# NixieTherm_v1_03.net
KiCad netlist of a schematic drawn in EAGLE
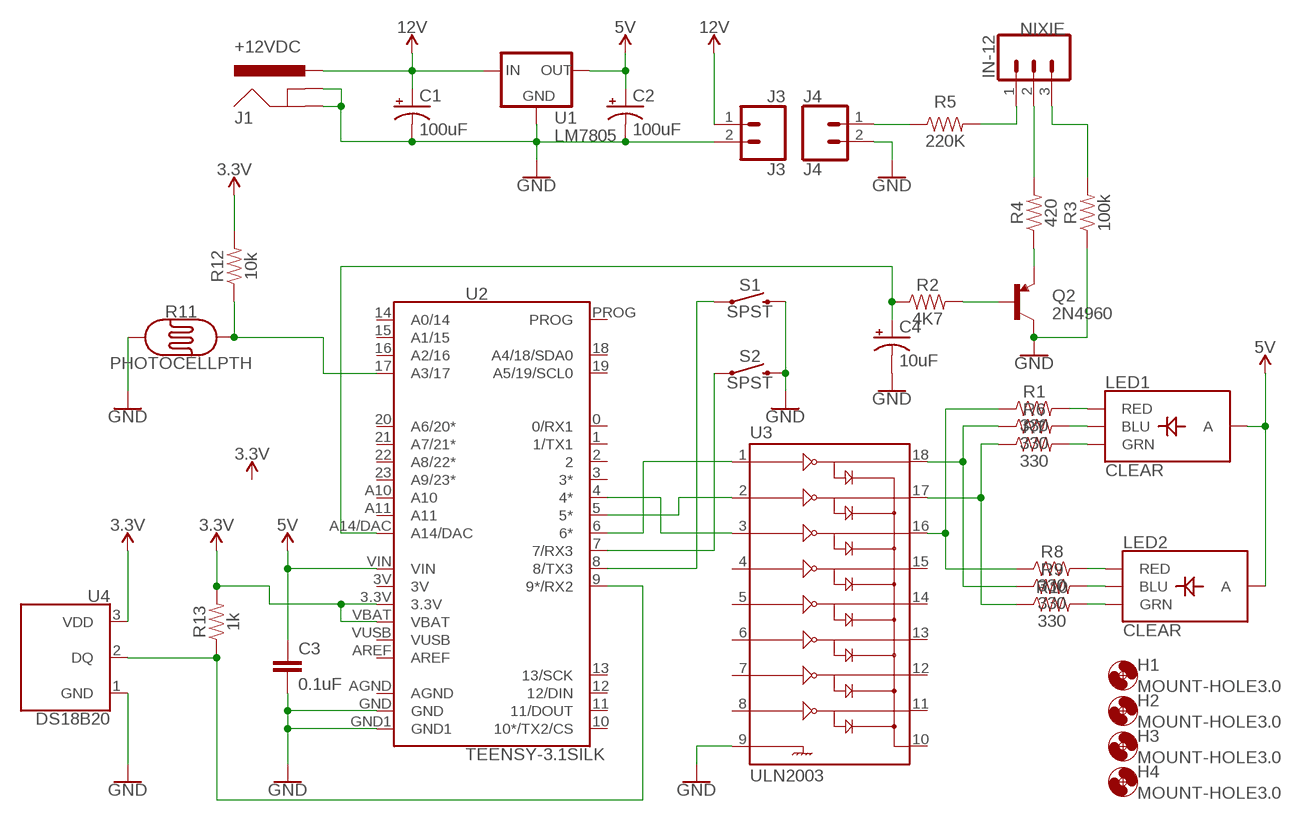
[diagram p0: schematic, sheet 1]

(export (version "E")
  (design (tool "Eeschema 10.0.6"))
  (components
    (comp (ref "C1")
      (value "100uF")
      (footprint "eagle-import:CPOL-RADIAL-2.5MM-6.5MM")
      (libsource (lib "eagle-import") (part "100UF-POLAR-RADIAL-2.5MM-25V-20%"))
    )
    (comp (ref "C2")
      (value "100uF")
      (footprint "eagle-import:CPOL-RADIAL-2.5MM-6.5MM")
      (libsource (lib "eagle-import") (part "100UF-POLAR-RADIAL-2.5MM-25V-20%"))
    )
    (comp (ref "C3")
      (value "0.1uF")
      (footprint "eagle-import:CAP-PTH-SMALL-KIT")
      (libsource (lib "eagle-import") (part "0.1UF-KIT-EZ-50V-20%"))
    )
    (comp (ref "C4")
      (value "10uF")
      (footprint "eagle-import:CPOL-RADIAL-2.5MM-5MM")
      (libsource (lib "eagle-import") (part "10UF-POLAR-RADIAL-2.5MM-25V-20%"))
    )
    (comp (ref "H1")
      (value "MOUNT-HOLE3.0")
      (footprint "eagle-import:3,0")
      (libsource (lib "eagle-import") (part "MOUNT-HOLE3.0"))
    )
    (comp (ref "H2")
      (value "MOUNT-HOLE3.0")
      (footprint "eagle-import:3,0")
      (libsource (lib "eagle-import") (part "MOUNT-HOLE3.0"))
    )
    (comp (ref "H3")
      (value "MOUNT-HOLE3.0")
      (footprint "eagle-import:3,0")
      (libsource (lib "eagle-import") (part "MOUNT-HOLE3.0"))
    )
    (comp (ref "H4")
      (value "MOUNT-HOLE3.0")
      (footprint "eagle-import:3,0")
      (libsource (lib "eagle-import") (part "MOUNT-HOLE3.0"))
    )
    (comp (ref "J1")
      (value "+12VDC")
      (footprint "eagle-import:POWER_JACK_PTH")
      (libsource (lib "eagle-import") (part "POWER_JACK"))
    )
    (comp (ref "J3")
      (value "J3")
      (footprint "eagle-import:1X02")
      (libsource (lib "eagle-import") (part "CONN_02"))
    )
    (comp (ref "J4")
      (value "J4")
      (footprint "eagle-import:1X02")
      (libsource (lib "eagle-import") (part "CONN_02"))
    )
    (comp (ref "LED1")
      (value "CLEAR")
      (footprint "eagle-import:LED-RGB-THRU")
      (libsource (lib "eagle-import") (part "LED-RGB-CACLEAR"))
    )
    (comp (ref "LED2")
      (value "CLEAR")
      (footprint "eagle-import:LED-RGB-THRU")
      (libsource (lib "eagle-import") (part "LED-RGB-CACLEAR"))
    )
    (comp (ref "NIXIE")
      (value "IN-12")
      (footprint "eagle-import:1X03_NO_SILK")
      (libsource (lib "eagle-import") (part "CONN_031X03_NO_SILK"))
    )
    (comp (ref "Q2")
      (value "2N4960")
      (footprint "eagle-import:TO-92")
      (libsource (lib "eagle-import") (part "TRANSISTOR_PNPTO92"))
    )
    (comp (ref "R1")
      (value "330")
      (footprint "eagle-import:AXIAL-0.3")
      (libsource (lib "eagle-import") (part "1KOHM-HORIZ-1/4W-1%"))
    )
    (comp (ref "R2")
      (value "4K7")
      (footprint "eagle-import:AXIAL-0.3")
      (libsource (lib "eagle-import") (part "100KOHM-HORIZ-1/4W-1%"))
    )
    (comp (ref "R3")
      (value "100k")
      (footprint "eagle-import:AXIAL-0.3")
      (libsource (lib "eagle-import") (part "100KOHM-HORIZ-1/4W-1%"))
    )
    (comp (ref "R4")
      (value "420")
      (footprint "eagle-import:AXIAL-0.3")
      (libsource (lib "eagle-import") (part "100KOHM-HORIZ-1/4W-1%"))
    )
    (comp (ref "R5")
      (value "220K")
      (footprint "eagle-import:AXIAL-0.3")
      (libsource (lib "eagle-import") (part "100KOHM-HORIZ-1/4W-1%"))
    )
    (comp (ref "R6")
      (value "330")
      (footprint "eagle-import:AXIAL-0.3")
      (libsource (lib "eagle-import") (part "1KOHM-HORIZ-1/4W-1%"))
    )
    (comp (ref "R7")
      (value "330")
      (footprint "eagle-import:AXIAL-0.3")
      (libsource (lib "eagle-import") (part "1KOHM-HORIZ-1/4W-1%"))
    )
    (comp (ref "R8")
      (value "330")
      (footprint "eagle-import:AXIAL-0.3")
      (libsource (lib "eagle-import") (part "1KOHM-HORIZ-1/4W-1%"))
    )
    (comp (ref "R9")
      (value "330")
      (footprint "eagle-import:AXIAL-0.3")
      (libsource (lib "eagle-import") (part "1KOHM-HORIZ-1/4W-1%"))
    )
    (comp (ref "R10")
      (value "330")
      (footprint "eagle-import:AXIAL-0.3")
      (libsource (lib "eagle-import") (part "1KOHM-HORIZ-1/4W-1%"))
    )
    (comp (ref "R11")
      (value "PHOTOCELLPTH")
      (footprint "eagle-import:PHOTOCELL")
      (libsource (lib "eagle-import") (part "PHOTOCELLPTH"))
    )
    (comp (ref "R12")
      (value "10k")
      (footprint "eagle-import:AXIAL-0.3")
      (libsource (lib "eagle-import") (part "10KOHM-HORIZ-1/4W-1%"))
    )
    (comp (ref "R13")
      (value "1k")
      (footprint "eagle-import:AXIAL-0.3")
      (libsource (lib "eagle-import") (part "1KOHM-HORIZ-1/4W-1%"))
    )
    (comp (ref "S1")
      (value "SPST")
      (footprint "eagle-import:TACTILE_SWITCH_PTH_6.0MM")
      (libsource (lib "eagle-import") (part "MOMENTARY-SWITCH-SPST-PTH-6.0MM"))
    )
    (comp (ref "S2")
      (value "SPST")
      (footprint "eagle-import:TACTILE_SWITCH_PTH_6.0MM")
      (libsource (lib "eagle-import") (part "MOMENTARY-SWITCH-SPST-PTH-6.0MM"))
    )
    (comp (ref "U1")
      (value "LM7805")
      (footprint "eagle-import:TO-220-ALT")
      (libsource (lib "eagle-import") (part "V_REG_78XX-TO-220"))
    )
    (comp (ref "U2")
      (value "TEENSY-3.1SILK")
      (footprint "eagle-import:TEENSY-3.1")
      (libsource (lib "eagle-import") (part "TEENSY-3.1SILK"))
    )
    (comp (ref "U3")
      (value "ULN2003")
      (footprint "eagle-import:DIL18")
      (libsource (lib "eagle-import") (part "ULN2803DIP"))
    )
    (comp (ref "U4")
      (value "DS18B20")
      (footprint "eagle-import:TO-92-AMMO")
      (libsource (lib "eagle-import") (part "DS18B20"))
    )
  )
  (nets
    (net (code "1") (name "/3V") (class "Default")
      (node (ref "U2") (pin "3V") (pinfunction "3V_3V") (pintype "power_in"))
    )
    (net (code "2") (name "/AGND") (class "Default")
      (node (ref "U2") (pin "AGND") (pinfunction "AGND_AGND") (pintype "power_in"))
    )
    (net (code "3") (name "/VUSB") (class "Default")
      (node (ref "U2") (pin "VUSB") (pinfunction "VUSB_VUSB") (pintype "power_in"))
    )
    (net (code "4") (name "3.3V") (class "Default")
      (node (ref "R12") (pin "P$2") (pinfunction "2_P$2") (pintype "passive"))
      (node (ref "R13") (pin "P$2") (pinfunction "2_P$2") (pintype "passive"))
      (node (ref "U2") (pin "3.3V") (pinfunction "3.3V_3.3V") (pintype "power_in"))
      (node (ref "U2") (pin "VBAT") (pinfunction "VBAT_VBAT") (pintype "power_in"))
      (node (ref "U4") (pin "3") (pinfunction "VDD_3") (pintype "power_in"))
    )
    (net (code "5") (name "5V") (class "Default")
      (node (ref "C2") (pin "1") (pinfunction "+_1") (pintype "passive"))
      (node (ref "C3") (pin "1") (pinfunction "1_1") (pintype "passive"))
      (node (ref "LED1") (pin "2") (pinfunction "A_2") (pintype "bidirectional"))
      (node (ref "LED2") (pin "2") (pinfunction "A_2") (pintype "bidirectional"))
      (node (ref "U1") (pin "OUT") (pinfunction "OUT_OUT") (pintype "passive"))
      (node (ref "U2") (pin "VIN") (pinfunction "VIN_VIN") (pintype "power_in"))
    )
    (net (code "6") (name "12V") (class "Default")
      (node (ref "C1") (pin "1") (pinfunction "+_1") (pintype "passive"))
      (node (ref "J1") (pin "PWR") (pinfunction "PWR_PWR") (pintype "bidirectional"))
      (node (ref "J3") (pin "1") (pinfunction "1_1") (pintype "passive"))
      (node (ref "U1") (pin "IN") (pinfunction "IN_IN") (pintype "input"))
    )
    (net (code "7") (name "GND") (class "Default")
      (node (ref "C1") (pin "2") (pinfunction "-_2") (pintype "passive"))
      (node (ref "C2") (pin "2") (pinfunction "-_2") (pintype "passive"))
      (node (ref "C3") (pin "2") (pinfunction "2_2") (pintype "passive"))
      (node (ref "C4") (pin "2") (pinfunction "-_2") (pintype "passive"))
      (node (ref "J1") (pin "GND") (pinfunction "GND_GND") (pintype "bidirectional"))
      (node (ref "J1") (pin "GNDBREAK") (pinfunction "GNDBREAK_GNDBREAK") (pintype "bidirectional"))
      (node (ref "J3") (pin "2") (pinfunction "2_2") (pintype "passive"))
      (node (ref "J4") (pin "2") (pinfunction "2_2") (pintype "passive"))
      (node (ref "Q2") (pin "3") (pinfunction "C_3") (pintype "passive"))
      (node (ref "R11") (pin "1") (pinfunction "P$1_1") (pintype "bidirectional"))
      (node (ref "R3") (pin "P$1") (pinfunction "1_P$1") (pintype "passive"))
      (node (ref "S1") (pin "3") (pinfunction "2_3") (pintype "passive"))
      (node (ref "S2") (pin "3") (pinfunction "2_3") (pintype "passive"))
      (node (ref "U1") (pin "GND") (pinfunction "GND_GND") (pintype "input"))
      (node (ref "U2") (pin "GND") (pinfunction "GND_GND") (pintype "power_in"))
      (node (ref "U2") (pin "GND1") (pinfunction "GND1_GND1") (pintype "power_in"))
      (node (ref "U3") (pin "9") (pinfunction "9_9") (pintype "bidirectional"))
      (node (ref "U4") (pin "1") (pinfunction "GND_1") (pintype "power_in"))
    )
    (net (code "8") (name "Net-(C4-+)") (class "Default")
      (node (ref "C4") (pin "1") (pinfunction "+_1") (pintype "passive"))
      (node (ref "R2") (pin "P$1") (pinfunction "1_P$1") (pintype "passive"))
      (node (ref "U2") (pin "A14/DAC") (pinfunction "A14/DAC_A14/DAC") (pintype "bidirectional"))
    )
    (net (code "9") (name "Net-(LED1-BLU)") (class "Default")
      (node (ref "LED1") (pin "4") (pinfunction "BLU_4") (pintype "bidirectional"))
      (node (ref "R6") (pin "P$2") (pinfunction "2_P$2") (pintype "passive"))
    )
    (net (code "10") (name "Net-(LED1-GRN)") (class "Default")
      (node (ref "LED1") (pin "3") (pinfunction "GRN_3") (pintype "bidirectional"))
      (node (ref "R7") (pin "P$2") (pinfunction "2_P$2") (pintype "passive"))
    )
    (net (code "11") (name "Net-(LED1-RED)") (class "Default")
      (node (ref "LED1") (pin "1") (pinfunction "RED_1") (pintype "bidirectional"))
      (node (ref "R1") (pin "P$2") (pinfunction "2_P$2") (pintype "passive"))
    )
    (net (code "12") (name "Net-(LED2-BLU)") (class "Default")
      (node (ref "LED2") (pin "4") (pinfunction "BLU_4") (pintype "bidirectional"))
      (node (ref "R9") (pin "P$2") (pinfunction "2_P$2") (pintype "passive"))
    )
    (net (code "13") (name "Net-(LED2-GRN)") (class "Default")
      (node (ref "LED2") (pin "3") (pinfunction "GRN_3") (pintype "bidirectional"))
      (node (ref "R10") (pin "P$2") (pinfunction "2_P$2") (pintype "passive"))
    )
    (net (code "14") (name "Net-(LED2-RED)") (class "Default")
      (node (ref "LED2") (pin "1") (pinfunction "RED_1") (pintype "bidirectional"))
      (node (ref "R8") (pin "P$2") (pinfunction "2_P$2") (pintype "passive"))
    )
    (net (code "15") (name "Net-(Q2-B)") (class "Default")
      (node (ref "Q2") (pin "2") (pinfunction "B_2") (pintype "passive"))
      (node (ref "R2") (pin "P$2") (pinfunction "2_P$2") (pintype "passive"))
    )
    (net (code "16") (name "Net-(Q2-E)") (class "Default")
      (node (ref "Q2") (pin "1") (pinfunction "E_1") (pintype "passive"))
      (node (ref "R4") (pin "P$1") (pinfunction "1_P$1") (pintype "passive"))
    )
    (net (code "17") (name "Net-(R1-1)") (class "Default")
      (node (ref "R1") (pin "P$1") (pinfunction "1_P$1") (pintype "passive"))
      (node (ref "R8") (pin "P$1") (pinfunction "1_P$1") (pintype "passive"))
      (node (ref "U3") (pin "16") (pinfunction "16_16") (pintype "bidirectional"))
    )
    (net (code "18") (name "Net-(R3-2)") (class "Default")
      (node (ref "NIXIE") (pin "3") (pinfunction "3_3") (pintype "passive"))
      (node (ref "R3") (pin "P$2") (pinfunction "2_P$2") (pintype "passive"))
    )
    (net (code "19") (name "Net-(R4-2)") (class "Default")
      (node (ref "NIXIE") (pin "2") (pinfunction "2_2") (pintype "passive"))
      (node (ref "R4") (pin "P$2") (pinfunction "2_P$2") (pintype "passive"))
    )
    (net (code "20") (name "Net-(R5-1)") (class "Default")
      (node (ref "J4") (pin "1") (pinfunction "1_1") (pintype "passive"))
      (node (ref "R5") (pin "P$1") (pinfunction "1_P$1") (pintype "passive"))
    )
    (net (code "21") (name "Net-(R5-2)") (class "Default")
      (node (ref "NIXIE") (pin "1") (pinfunction "1_1") (pintype "passive"))
      (node (ref "R5") (pin "P$2") (pinfunction "2_P$2") (pintype "passive"))
    )
    (net (code "22") (name "Net-(R6-1)") (class "Default")
      (node (ref "R6") (pin "P$1") (pinfunction "1_P$1") (pintype "passive"))
      (node (ref "R9") (pin "P$1") (pinfunction "1_P$1") (pintype "passive"))
      (node (ref "U3") (pin "18") (pinfunction "18_18") (pintype "bidirectional"))
    )
    (net (code "23") (name "Net-(R10-1)") (class "Default")
      (node (ref "R10") (pin "P$1") (pinfunction "1_P$1") (pintype "passive"))
      (node (ref "R7") (pin "P$1") (pinfunction "1_P$1") (pintype "passive"))
      (node (ref "U3") (pin "17") (pinfunction "17_17") (pintype "bidirectional"))
    )
    (net (code "24") (name "Net-(R11-P$2)") (class "Default")
      (node (ref "R11") (pin "2") (pinfunction "P$2_2") (pintype "bidirectional"))
      (node (ref "R12") (pin "P$1") (pinfunction "1_P$1") (pintype "passive"))
      (node (ref "U2") (pin "17") (pinfunction "A3/17_17") (pintype "bidirectional"))
    )
    (net (code "25") (name "Net-(R13-1)") (class "Default")
      (node (ref "R13") (pin "P$1") (pinfunction "1_P$1") (pintype "passive"))
      (node (ref "U2") (pin "9") (pinfunction "9*/RX2_9") (pintype "bidirectional"))
      (node (ref "U4") (pin "2") (pinfunction "DQ_2") (pintype "bidirectional"))
    )
    (net (code "26") (name "Net-(U2-4*)") (class "Default")
      (node (ref "U2") (pin "4") (pinfunction "4*_4") (pintype "bidirectional"))
      (node (ref "U3") (pin "3") (pinfunction "3_3") (pintype "bidirectional"))
    )
    (net (code "27") (name "Net-(U2-5*)") (class "Default")
      (node (ref "U2") (pin "5") (pinfunction "5*_5") (pintype "bidirectional"))
      (node (ref "U3") (pin "2") (pinfunction "2_2") (pintype "bidirectional"))
    )
    (net (code "28") (name "Net-(U2-6*)") (class "Default")
      (node (ref "U2") (pin "6") (pinfunction "6*_6") (pintype "bidirectional"))
      (node (ref "U3") (pin "1") (pinfunction "1_1") (pintype "bidirectional"))
    )
    (net (code "29") (name "Net-(U2-7{slash}RX3)") (class "Default")
      (node (ref "S2") (pin "1") (pinfunction "1_1") (pintype "passive"))
      (node (ref "U2") (pin "7") (pinfunction "7/RX3_7") (pintype "bidirectional"))
    )
    (net (code "30") (name "Net-(U2-8{slash}TX3)") (class "Default")
      (node (ref "S1") (pin "1") (pinfunction "1_1") (pintype "passive"))
      (node (ref "U2") (pin "8") (pinfunction "8/TX3_8") (pintype "bidirectional"))
    )
    (net (code "31") (name "unconnected-(U2-0{slash}RX1-Pad0)") (class "Default")
      (node (ref "U2") (pin "0") (pinfunction "0/RX1_0") (pintype "bidirectional"))
    )
    (net (code "32") (name "unconnected-(U2-1{slash}TX1-Pad1)") (class "Default")
      (node (ref "U2") (pin "1") (pinfunction "1/TX1_1") (pintype "bidirectional"))
    )
    (net (code "33") (name "unconnected-(U2-3*-Pad3)") (class "Default")
      (node (ref "U2") (pin "3") (pinfunction "3*_3") (pintype "bidirectional"))
    )
    (net (code "34") (name "unconnected-(U2-10*{slash}TX2{slash}CS-Pad10)") (class "Default")
      (node (ref "U2") (pin "10") (pinfunction "10*/TX2/CS_10") (pintype "bidirectional"))
    )
    (net (code "35") (name "unconnected-(U2-11{slash}DOUT-Pad11)") (class "Default")
      (node (ref "U2") (pin "11") (pinfunction "11/DOUT_11") (pintype "bidirectional"))
    )
    (net (code "36") (name "unconnected-(U2-12{slash}DIN-Pad12)") (class "Default")
      (node (ref "U2") (pin "12") (pinfunction "12/DIN_12") (pintype "bidirectional"))
    )
    (net (code "37") (name "unconnected-(U2-13{slash}SCK-Pad13)") (class "Default")
      (node (ref "U2") (pin "13") (pinfunction "13/SCK_13") (pintype "bidirectional"))
    )
    (net (code "38") (name "unconnected-(U2-A0{slash}14-Pad14)") (class "Default")
      (node (ref "U2") (pin "14") (pinfunction "A0/14_14") (pintype "bidirectional"))
    )
    (net (code "39") (name "unconnected-(U2-A1{slash}15-Pad15)") (class "Default")
      (node (ref "U2") (pin "15") (pinfunction "A1/15_15") (pintype "bidirectional"))
    )
    (net (code "40") (name "unconnected-(U2-A2{slash}16-Pad16)") (class "Default")
      (node (ref "U2") (pin "16") (pinfunction "A2/16_16") (pintype "bidirectional"))
    )
    (net (code "41") (name "unconnected-(U2-A4{slash}18{slash}SDA0-Pad18)") (class "Default")
      (node (ref "U2") (pin "18") (pinfunction "A4/18/SDA0_18") (pintype "bidirectional"))
    )
    (net (code "42") (name "unconnected-(U2-A5{slash}19{slash}SCL0-Pad19)") (class "Default")
      (node (ref "U2") (pin "19") (pinfunction "A5/19/SCL0_19") (pintype "bidirectional"))
    )
    (net (code "43") (name "unconnected-(U2-A6{slash}20*-Pad20)") (class "Default")
      (node (ref "U2") (pin "20") (pinfunction "A6/20*_20") (pintype "bidirectional"))
    )
    (net (code "44") (name "unconnected-(U2-A7{slash}21*-Pad21)") (class "Default")
      (node (ref "U2") (pin "21") (pinfunction "A7/21*_21") (pintype "bidirectional"))
    )
    (net (code "45") (name "unconnected-(U2-A8{slash}22*-Pad22)") (class "Default")
      (node (ref "U2") (pin "22") (pinfunction "A8/22*_22") (pintype "bidirectional"))
    )
    (net (code "46") (name "unconnected-(U2-A9{slash}23*-Pad23)") (class "Default")
      (node (ref "U2") (pin "23") (pinfunction "A9/23*_23") (pintype "bidirectional"))
    )
    (net (code "47") (name "unconnected-(U2-Pad2)") (class "Default")
      (node (ref "U2") (pin "2") (pinfunction "2_2") (pintype "bidirectional"))
    )
    (net (code "48") (name "unconnected-(U2-PadA10)") (class "Default")
      (node (ref "U2") (pin "A10") (pinfunction "A10_A10") (pintype "bidirectional"))
    )
    (net (code "49") (name "unconnected-(U2-PadA11)") (class "Default")
      (node (ref "U2") (pin "A11") (pinfunction "A11_A11") (pintype "bidirectional"))
    )
    (net (code "50") (name "unconnected-(U2-PadAREF)") (class "Default")
      (node (ref "U2") (pin "AREF") (pinfunction "AREF_AREF") (pintype "bidirectional"))
    )
    (net (code "51") (name "unconnected-(U2-PadPROG)") (class "Default")
      (node (ref "U2") (pin "PROG") (pinfunction "PROG_PROG") (pintype "bidirectional"))
    )
    (net (code "52") (name "unconnected-(U3-Pad4)") (class "Default")
      (node (ref "U3") (pin "4") (pinfunction "4_4") (pintype "bidirectional"))
    )
    (net (code "53") (name "unconnected-(U3-Pad5)") (class "Default")
      (node (ref "U3") (pin "5") (pinfunction "5_5") (pintype "bidirectional"))
    )
    (net (code "54") (name "unconnected-(U3-Pad6)") (class "Default")
      (node (ref "U3") (pin "6") (pinfunction "6_6") (pintype "bidirectional"))
    )
    (net (code "55") (name "unconnected-(U3-Pad7)") (class "Default")
      (node (ref "U3") (pin "7") (pinfunction "7_7") (pintype "bidirectional"))
    )
    (net (code "56") (name "unconnected-(U3-Pad8)") (class "Default")
      (node (ref "U3") (pin "8") (pinfunction "8_8") (pintype "bidirectional"))
    )
    (net (code "57") (name "unconnected-(U3-Pad10)") (class "Default")
      (node (ref "U3") (pin "10") (pinfunction "10_10") (pintype "bidirectional"))
    )
    (net (code "58") (name "unconnected-(U3-Pad11)") (class "Default")
      (node (ref "U3") (pin "11") (pinfunction "11_11") (pintype "bidirectional"))
    )
    (net (code "59") (name "unconnected-(U3-Pad12)") (class "Default")
      (node (ref "U3") (pin "12") (pinfunction "12_12") (pintype "bidirectional"))
    )
    (net (code "60") (name "unconnected-(U3-Pad13)") (class "Default")
      (node (ref "U3") (pin "13") (pinfunction "13_13") (pintype "bidirectional"))
    )
    (net (code "61") (name "unconnected-(U3-Pad14)") (class "Default")
      (node (ref "U3") (pin "14") (pinfunction "14_14") (pintype "bidirectional"))
    )
    (net (code "62") (name "unconnected-(U3-Pad15)") (class "Default")
      (node (ref "U3") (pin "15") (pinfunction "15_15") (pintype "bidirectional"))
    )
  )
)
